# M5_Stick_YellowBox_Hat_2020-08-21_10-44-.net
KiCad netlist of a schematic drawn in EasyEDA
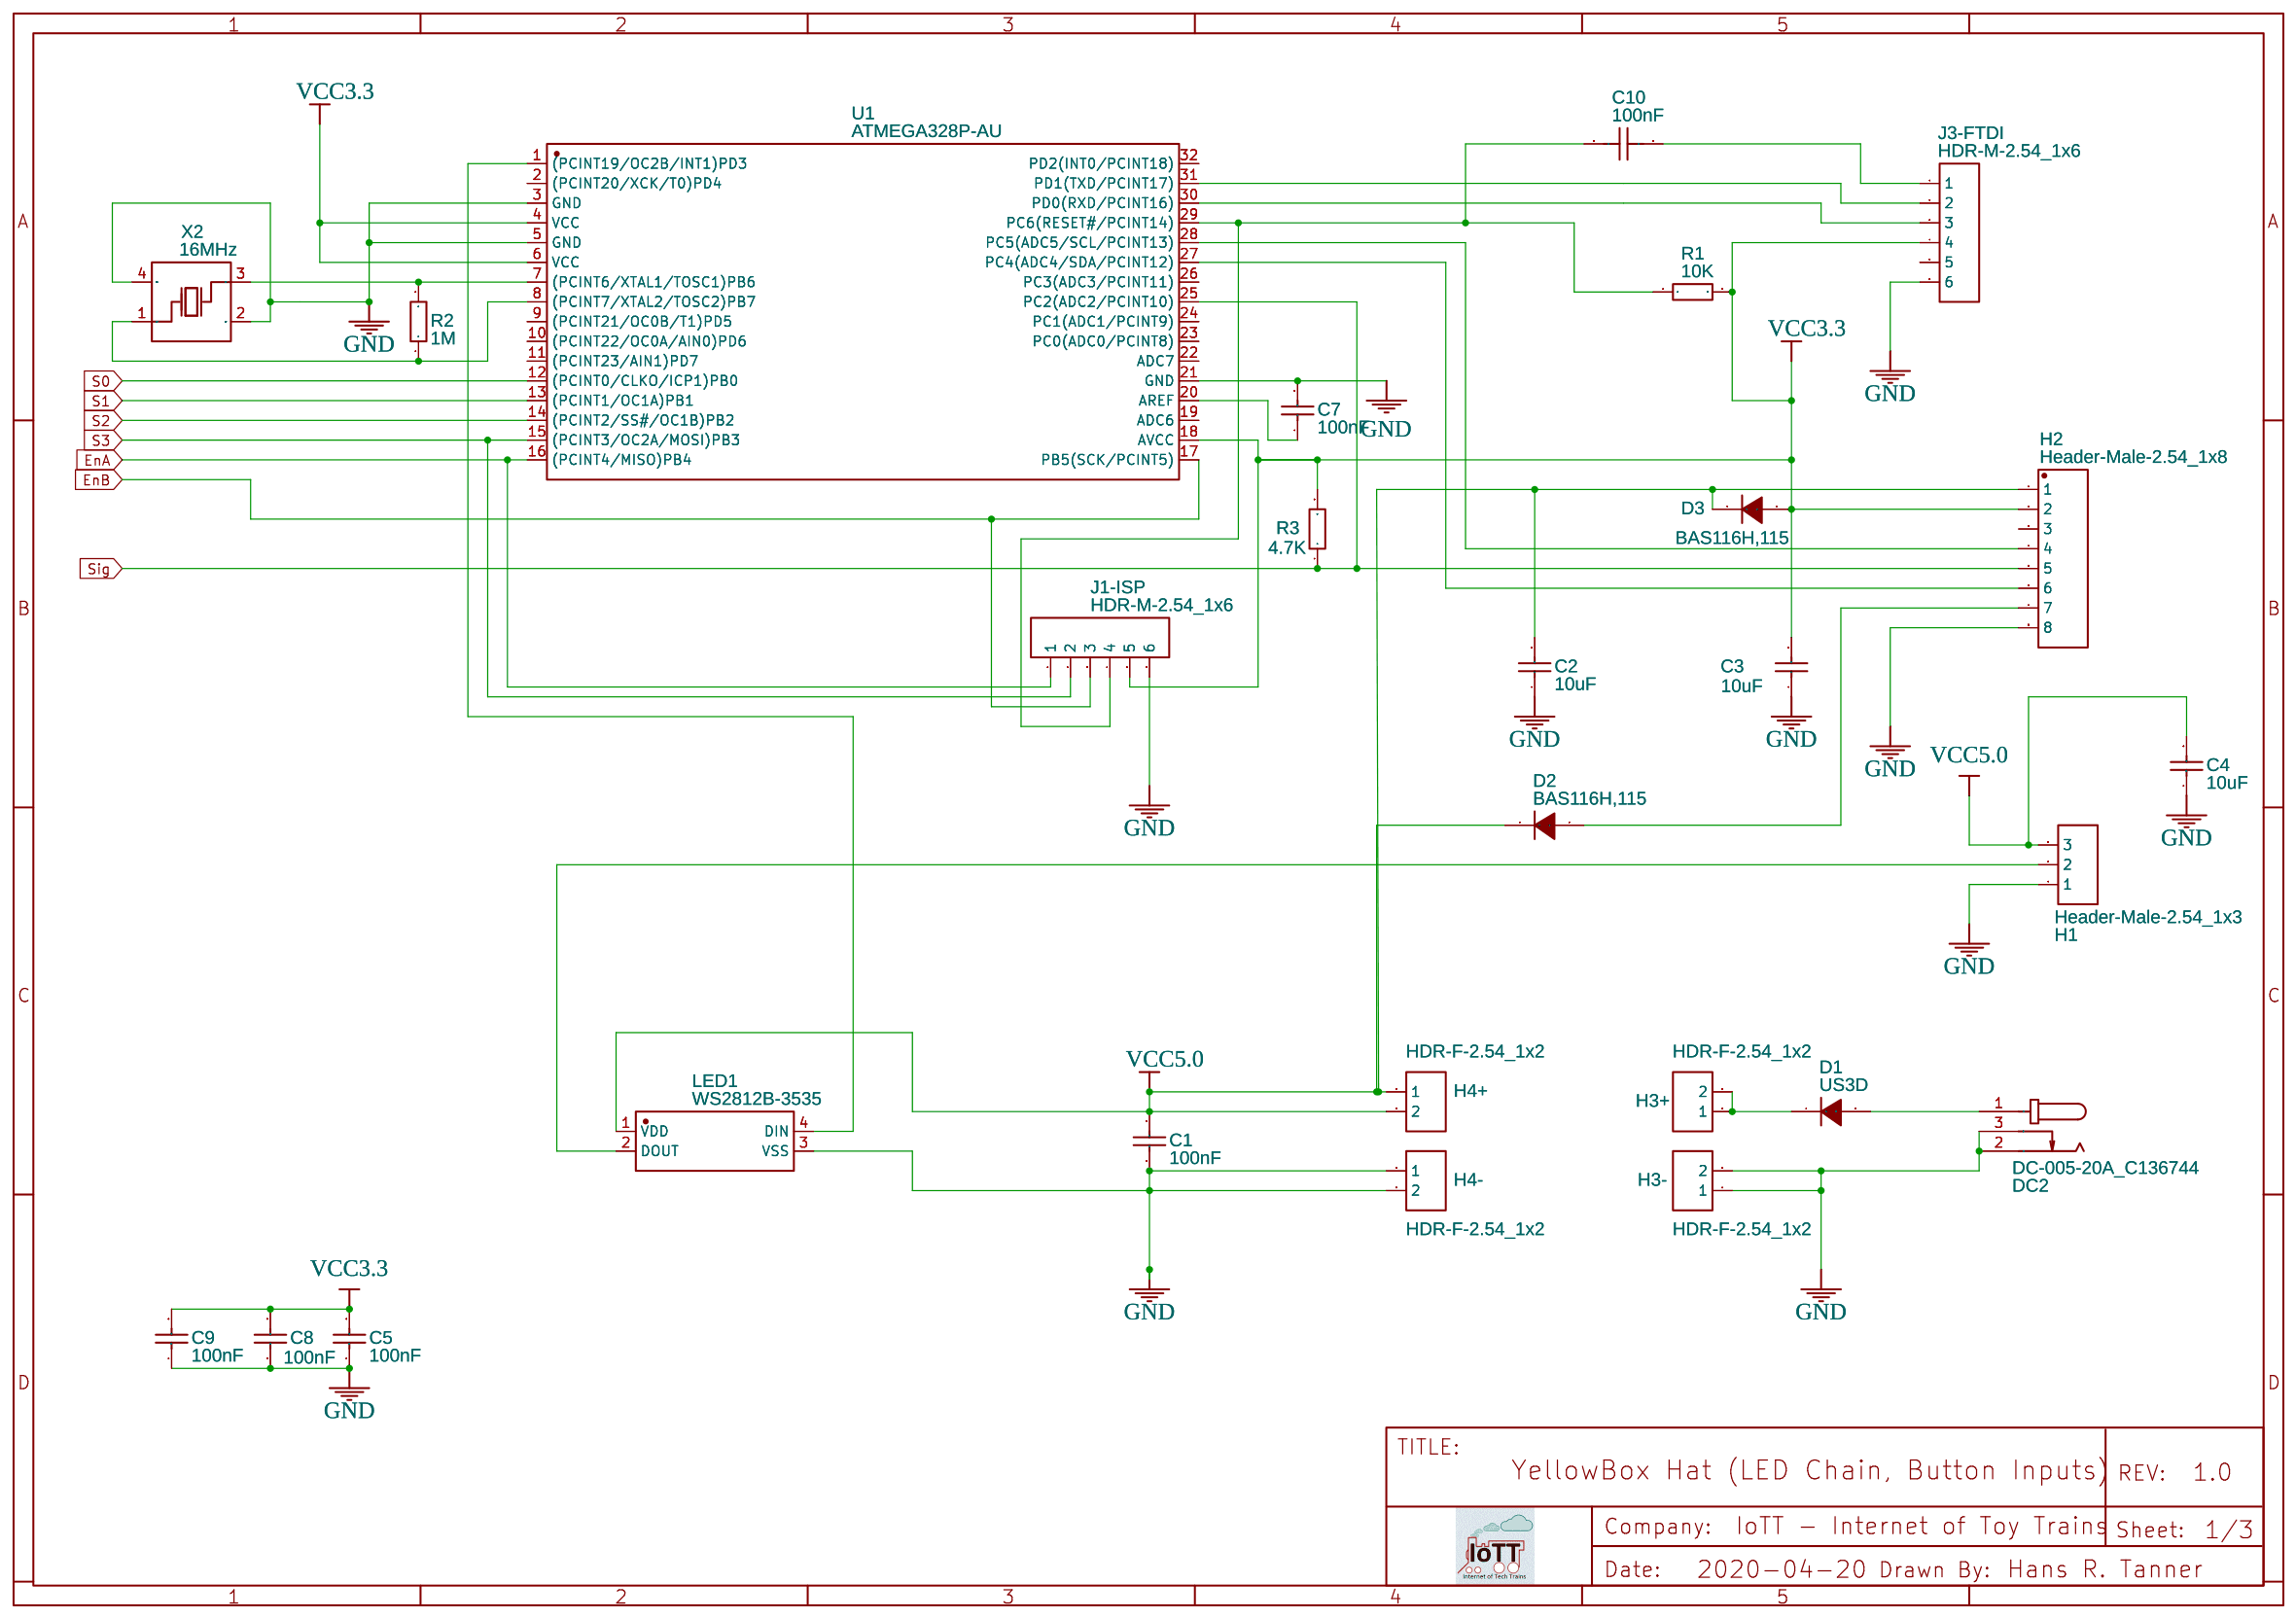
[diagram p0: YellowBox Hat P1]
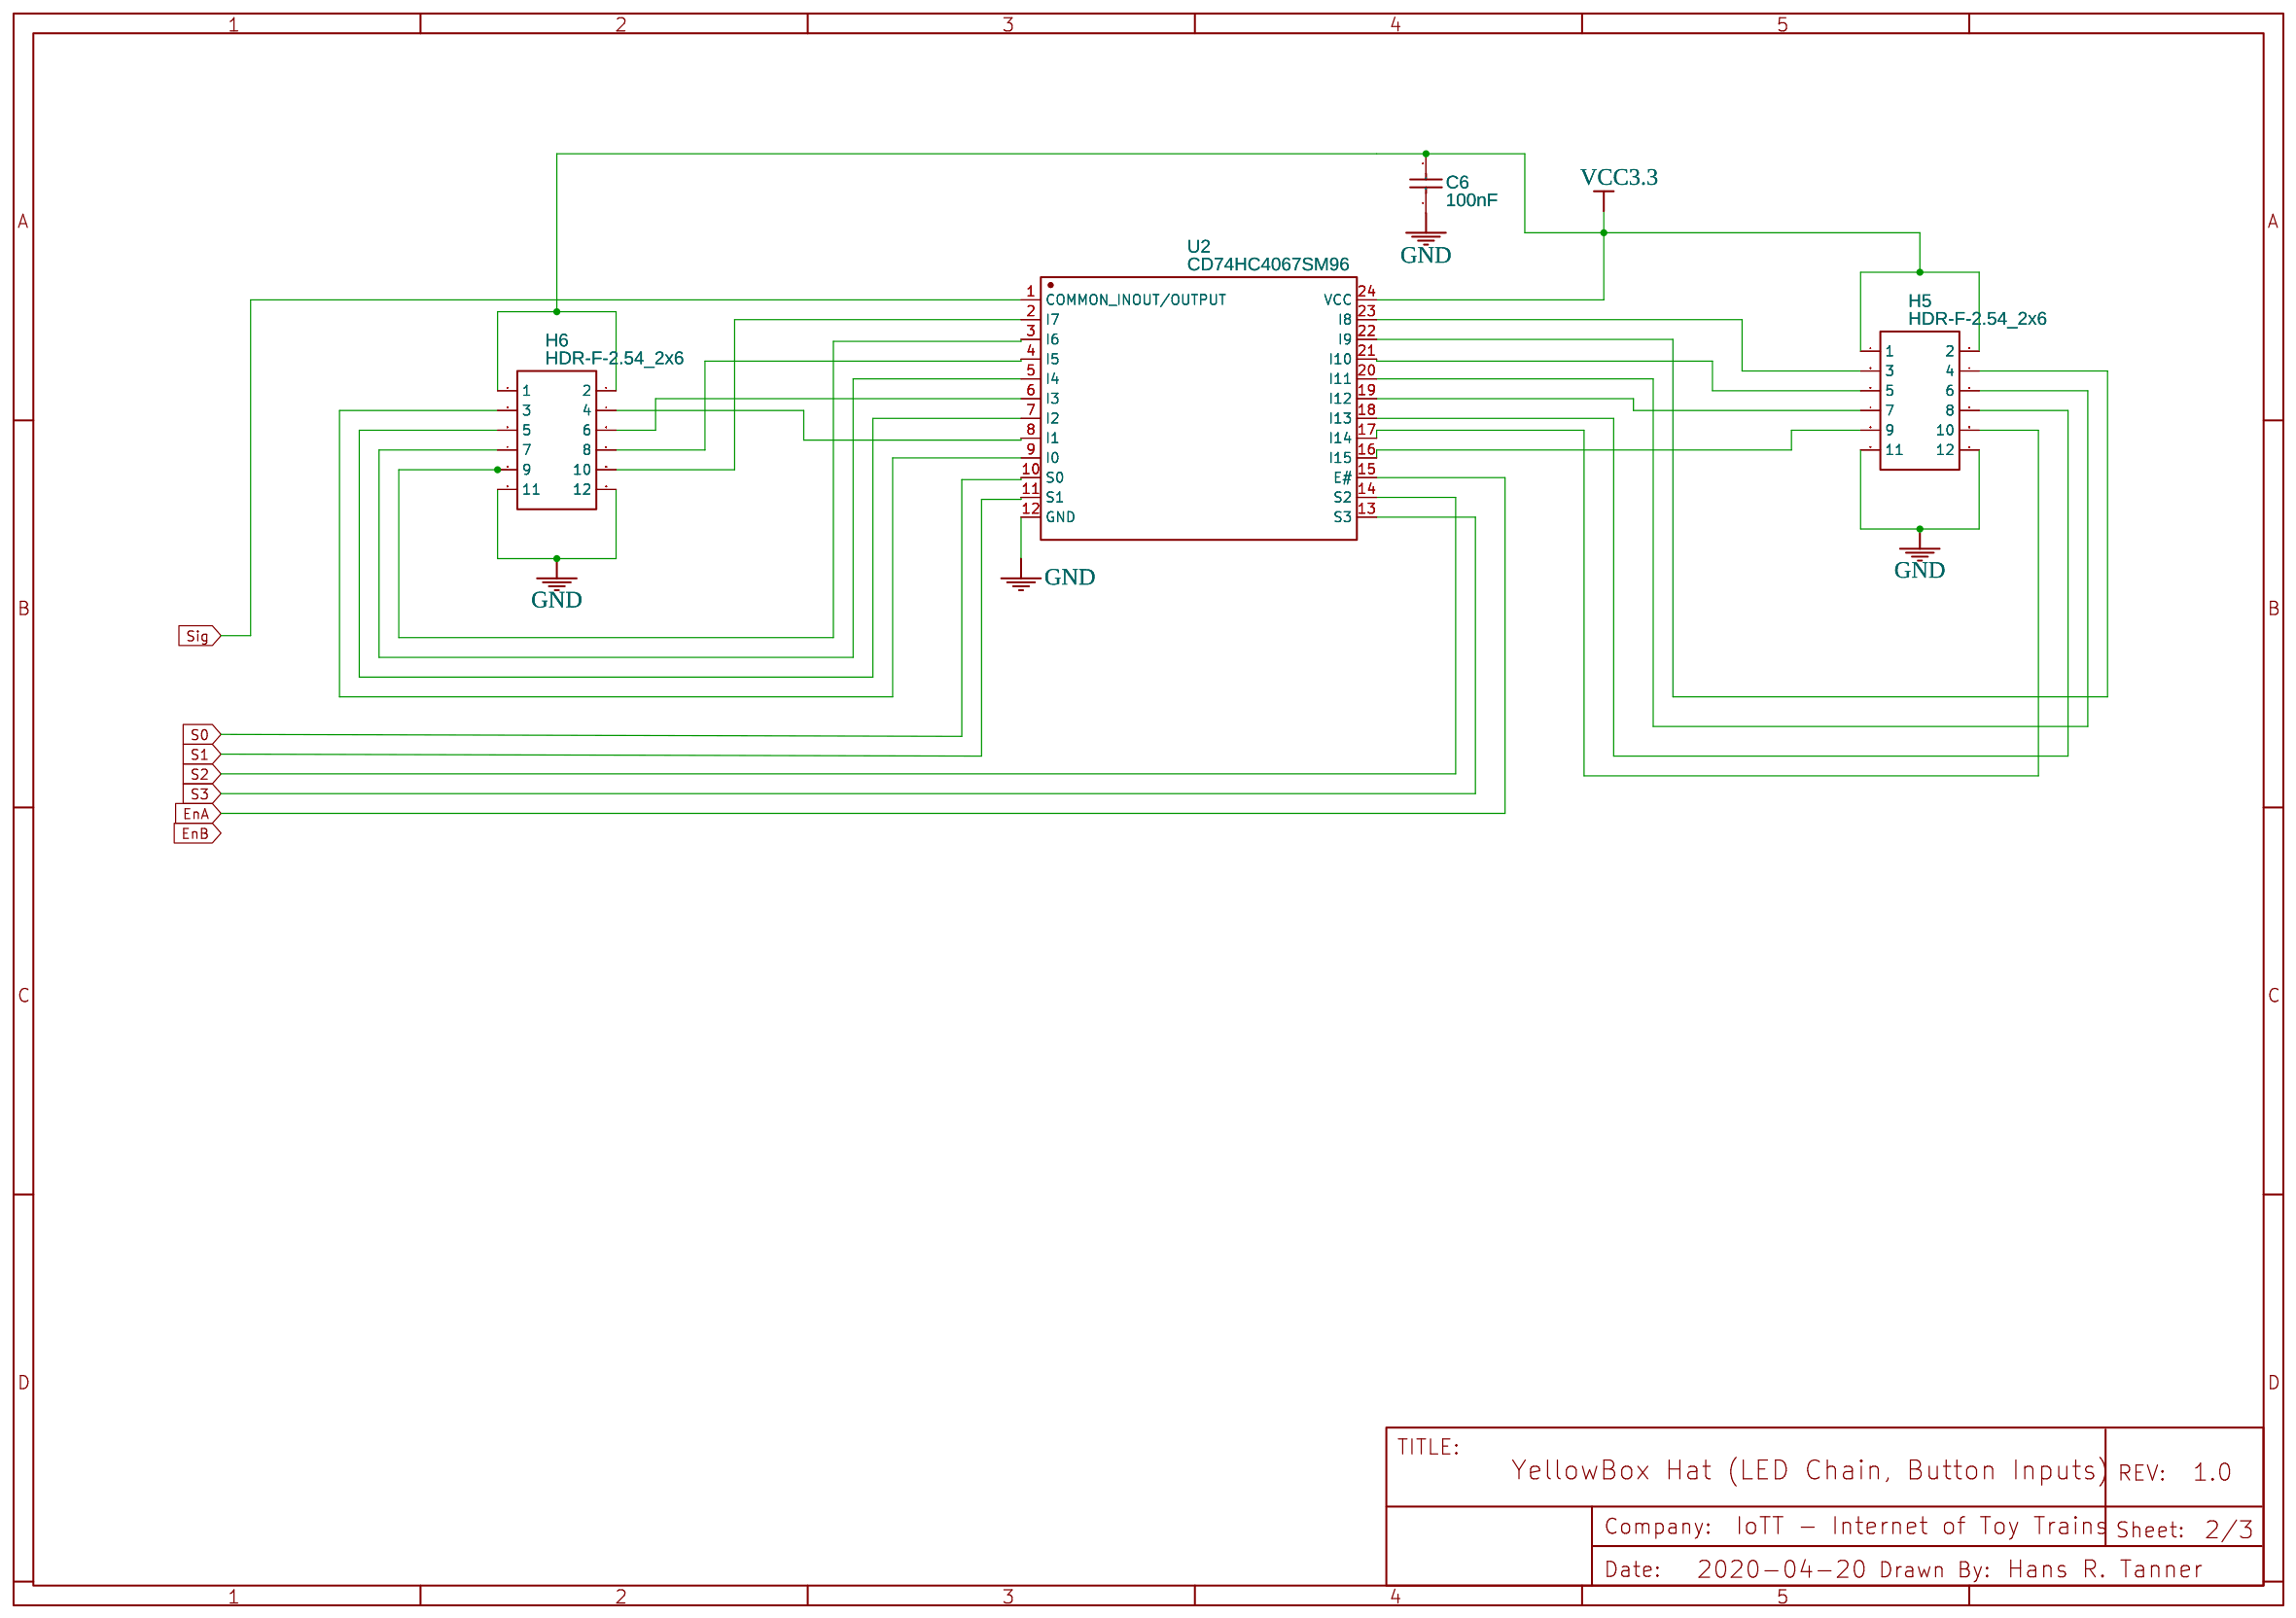
[diagram p1: YellowBox Hat P2]
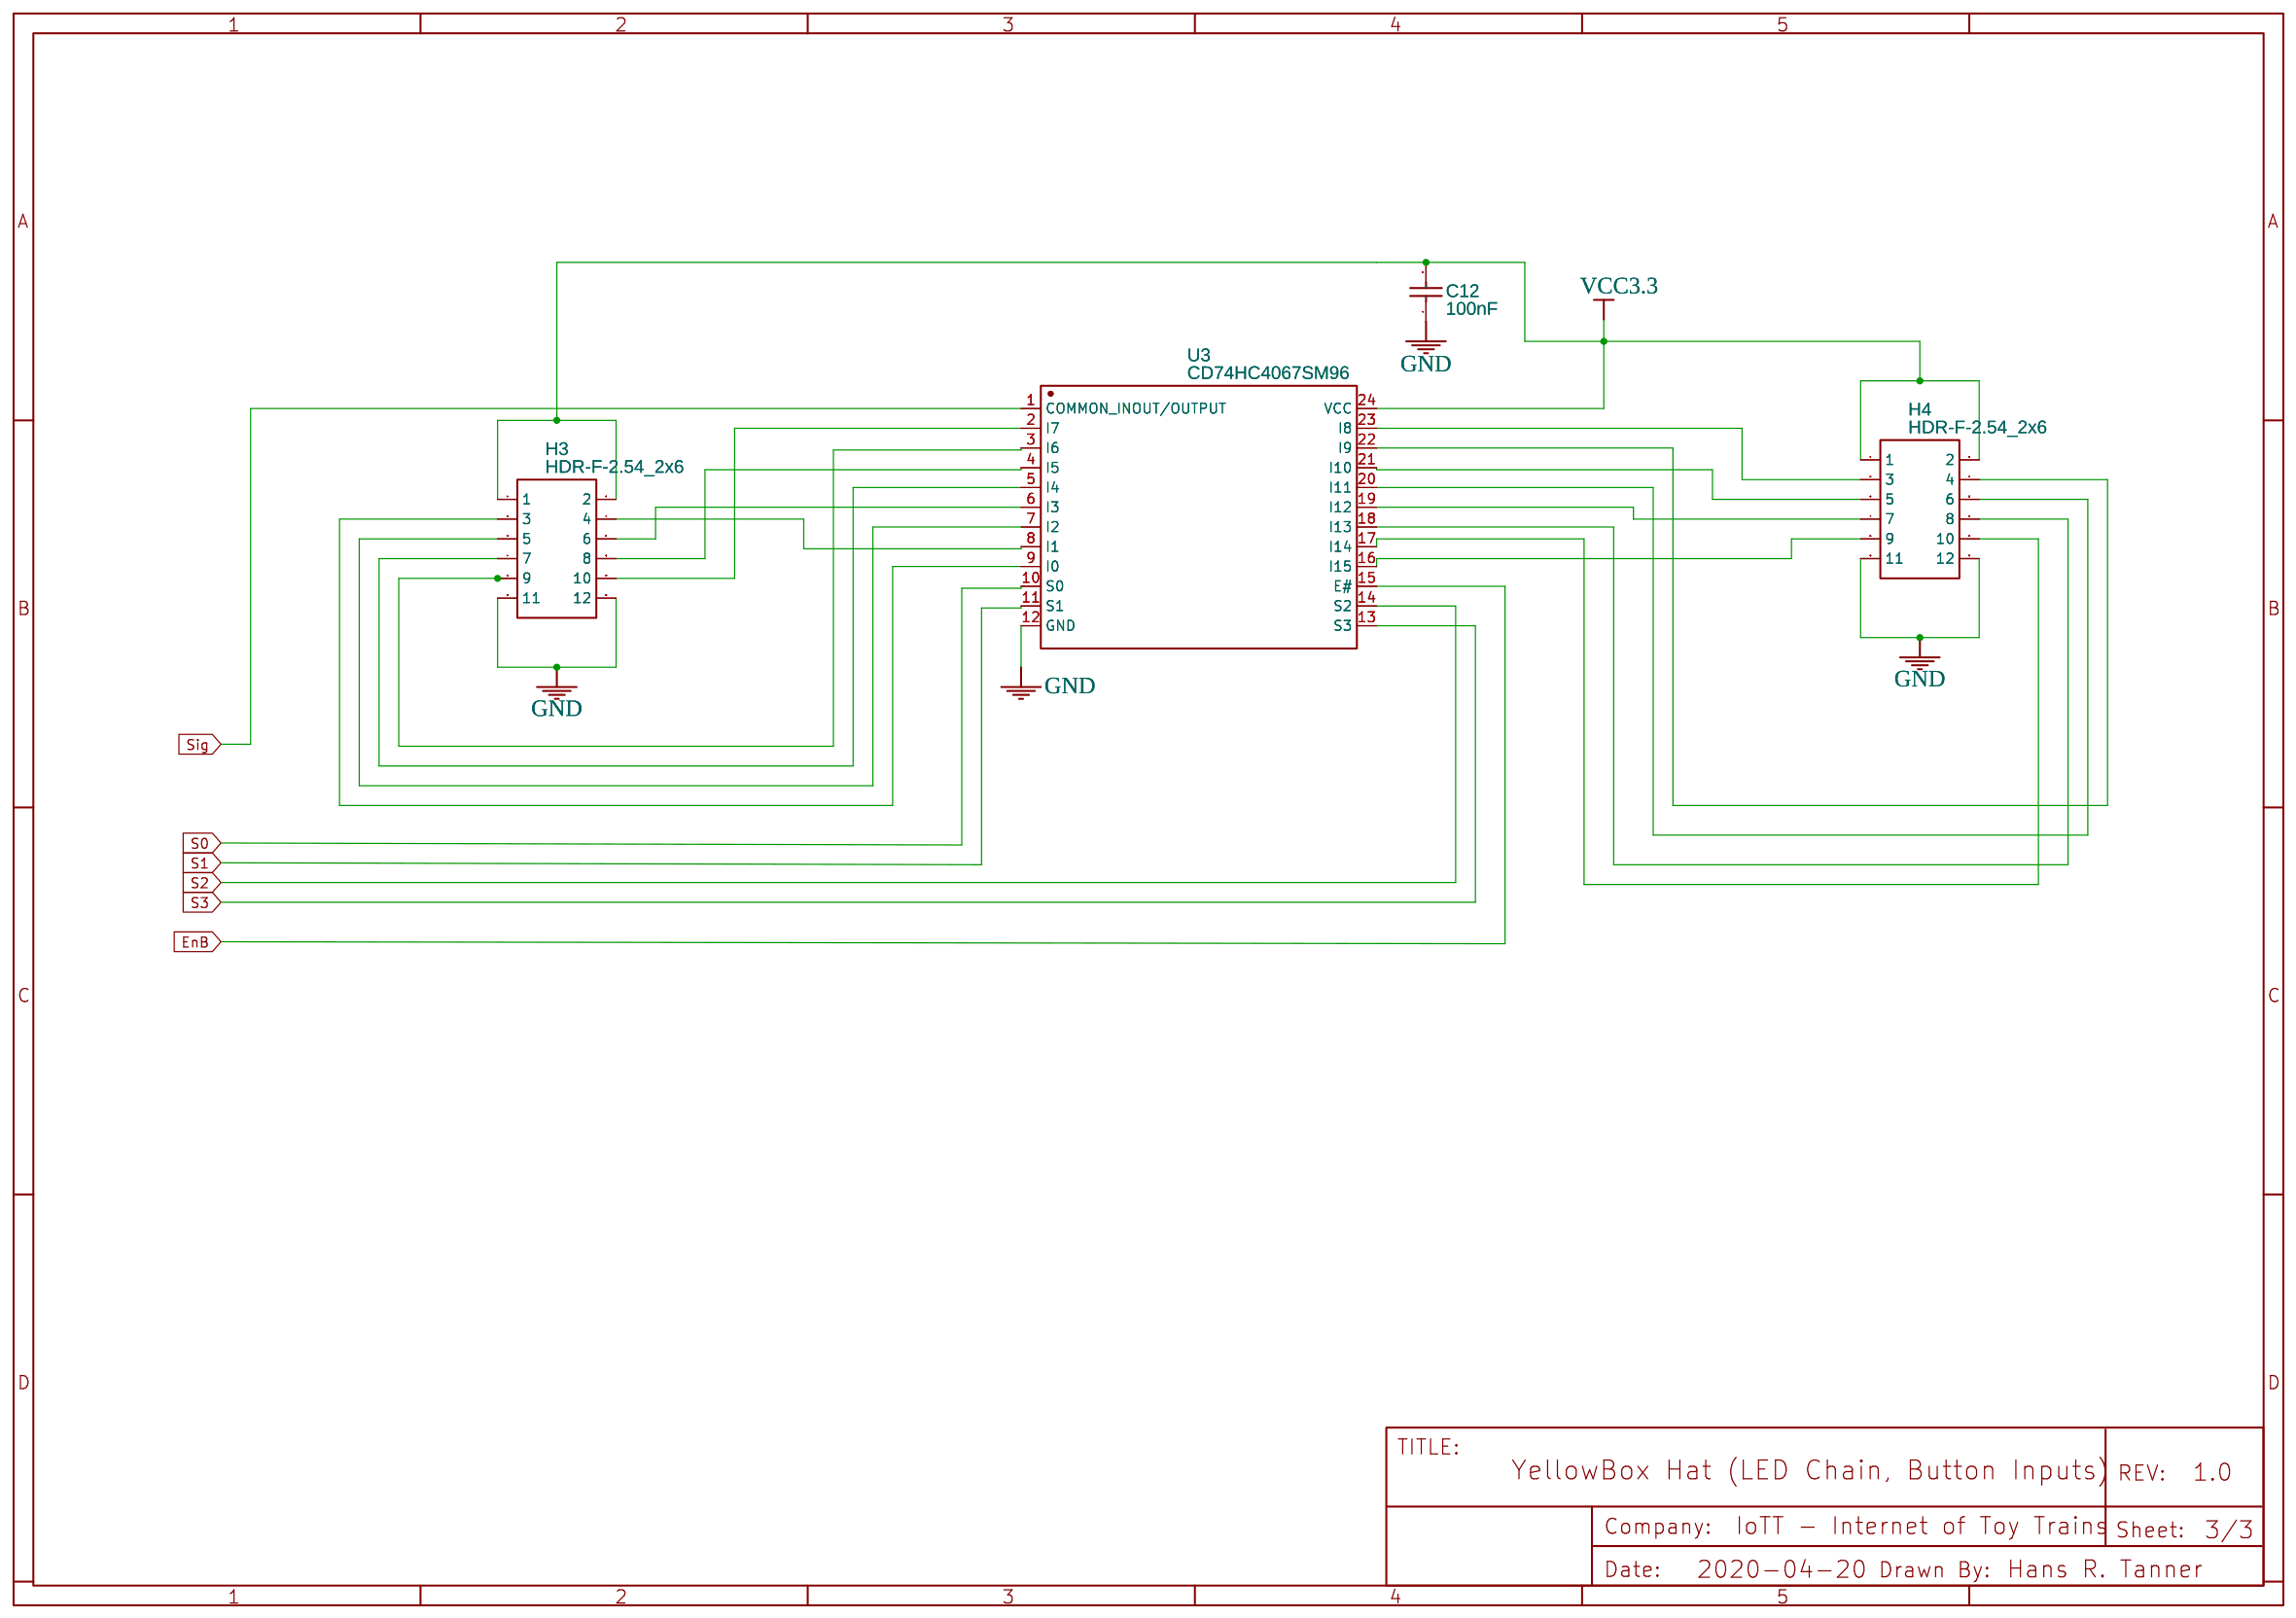
[diagram p2: YellowBox Hat P3]

(export (version "E")
  (design (tool "Eeschema 10.0.6"))
  (components
    (comp (ref "C1")
      (value "100nF")
      (fields
        (field (name "BOM_Manufacturer Part") "CL05B104KO5NNNC")
        (field (name "BOM_Supplier Part") "C1525")
      )
      (libsource (lib "") (part "CL05B104KO5NNNC"))
    )
    (comp (ref "C2")
      (value "10uF")
      (fields
        (field (name "BOM_Manufacturer Part") "CL21A106KAYNNNE")
        (field (name "BOM_Supplier Part") "C15850")
      )
      (libsource (lib "") (part "CL21A106KAYNNNE"))
    )
    (comp (ref "C3")
      (value "10uF")
      (fields
        (field (name "BOM_Manufacturer Part") "CL21A106KAYNNNE")
        (field (name "BOM_Supplier Part") "C15850")
      )
      (libsource (lib "") (part "CL21A106KAYNNNE"))
    )
    (comp (ref "C4")
      (value "10uF")
      (fields
        (field (name "BOM_Manufacturer Part") "CL21A106KAYNNNE")
        (field (name "BOM_Supplier Part") "C15850")
      )
      (libsource (lib "") (part "CL21A106KAYNNNE"))
    )
    (comp (ref "C5")
      (value "100nF")
      (fields
        (field (name "BOM_Manufacturer Part") "CL05B104KO5NNNC")
        (field (name "BOM_Supplier Part") "C1525")
      )
      (libsource (lib "") (part "CL05B104KO5NNNC"))
    )
    (comp (ref "C7")
      (value "100nF")
      (fields
        (field (name "BOM_Manufacturer Part") "CL05B104KO5NNNC")
        (field (name "BOM_Supplier Part") "C1525")
      )
      (libsource (lib "") (part "CL05B104KO5NNNC"))
    )
    (comp (ref "C8")
      (value "100nF")
      (fields
        (field (name "BOM_Manufacturer Part") "CL05B104KO5NNNC")
        (field (name "BOM_Supplier Part") "C1525")
      )
      (libsource (lib "") (part "CL05B104KO5NNNC"))
    )
    (comp (ref "C9")
      (value "100nF")
      (fields
        (field (name "BOM_Manufacturer Part") "CL05B104KO5NNNC")
        (field (name "BOM_Supplier Part") "C1525")
      )
      (libsource (lib "") (part "CL05B104KO5NNNC"))
    )
    (comp (ref "C10")
      (value "100nF")
      (fields
        (field (name "BOM_Manufacturer Part") "CC0603KRX7R9BB104")
        (field (name "BOM_Supplier Part") "C14663")
      )
      (libsource (lib "") (part "CC0603KRX7R9BB104"))
    )
    (comp (ref "D1")
      (value "US3D")
      (fields (field (name "BOM_Supplier Part") "C64964"))
      (libsource (lib "") (part "US3D"))
    )
    (comp (ref "D2")
      (value "BAS116H,115")
      (fields (field (name "BOM_Supplier Part") "C74210"))
      (libsource (lib "") (part "BAS116H,115"))
    )
    (comp (ref "D3")
      (value "BAS116H,115")
      (fields (field (name "BOM_Supplier Part") "C74210"))
      (libsource (lib "") (part "BAS116H,115"))
    )
    (comp (ref "DC2")
      (value "DC-005-20A_C136744")
      (fields
        (field (name "BOM_Manufacturer Part") "DC-005-20A")
        (field (name "BOM_Supplier Part") "C136744")
      )
      (libsource (lib "") (part "DC-005-20A_C136744"))
    )
    (comp (ref "H1")
      (value "Header-Male-2.54_1x3")
      (fields
        (field (name "BOM_Manufacturer Part") "Header2.54mm 1*3P")
        (field (name "BOM_Supplier Part") "C49257")
      )
      (libsource (lib "") (part "Header-Male-2.54_1x3"))
    )
    (comp (ref "H2")
      (value "Header-Male-2.54_1x8")
      (fields
        (field (name "BOM_Manufacturer Part") "210S-1*8P L=11.6MMGold-plated black")
        (field (name "BOM_Supplier Part") "C124381")
      )
      (libsource (lib "") (part "Header-Male-2.54_1x8"))
    )
    (comp (ref "H3+")
      (value "HDR-F-2.54_1x2")
      (fields (field (name "BOM_Supplier Part") "C49661"))
      (libsource (lib "") (part "HDR-F-2.54_1x2"))
    )
    (comp (ref "H3-")
      (value "HDR-F-2.54_1x2")
      (fields (field (name "BOM_Supplier Part") "C49661"))
      (libsource (lib "") (part "HDR-F-2.54_1x2_2"))
    )
    (comp (ref "H4+")
      (value "HDR-F-2.54_1x2")
      (fields (field (name "BOM_Supplier Part") "C49661"))
      (libsource (lib "") (part "HDR-F-2.54_1x2_3"))
    )
    (comp (ref "H4-")
      (value "HDR-F-2.54_1x2")
      (fields (field (name "BOM_Supplier Part") "C49661"))
      (libsource (lib "") (part "HDR-F-2.54_1x2_1"))
    )
    (comp (ref "J1-ISP")
      (value "HDR-M-2.54_1x6")
      (fields (field (name "BOM_Supplier Part") "C190819"))
      (libsource (lib "") (part "HDR-M-2.54_1x6"))
    )
    (comp (ref "J3-FTDI")
      (value "HDR-M-2.54_1x6")
      (fields (field (name "BOM_Supplier Part") "C190819"))
      (libsource (lib "") (part "HDR-M-2.54_1x6_1"))
    )
    (comp (ref "LED1")
      (value "WS2812B-3535")
      (fields (field (name "BOM_Supplier Part") "C114583"))
      (libsource (lib "") (part "WS2812B-3535"))
    )
    (comp (ref "R1")
      (value "10K")
      (fields
        (field (name "BOM_Manufacturer Part") "0402WGF1002TCE")
        (field (name "BOM_Supplier Part") "C25744")
      )
      (libsource (lib "") (part "0402WGF1002TCE"))
    )
    (comp (ref "R2")
      (value "1M")
      (fields
        (field (name "BOM_Manufacturer Part") "0402WGF1004TCE")
        (field (name "BOM_Supplier Part") "C26083")
      )
      (libsource (lib "") (part "0402WGF1004TCE"))
    )
    (comp (ref "R3")
      (value "4.7K")
      (fields
        (field (name "BOM_Manufacturer Part") "0603WAF4701T5E")
        (field (name "BOM_Supplier Part") "C23162")
      )
      (libsource (lib "") (part "0603WAF1001T5E"))
    )
    (comp (ref "U1")
      (value "ATMEGA328P-AU")
      (fields (field (name "BOM_Supplier Part") "C14877"))
      (libsource (lib "") (part "ATMEGA328P-AU"))
    )
    (comp (ref "X2")
      (value "16MHz")
      (fields
        (field (name "BOM_Manufacturer Part") "X322516MLB4SI")
        (field (name "BOM_Supplier Part") "C13738")
      )
      (libsource (lib "") (part "X322516MLB4SI"))
    )
    (comp (ref "C6")
      (value "100nF")
      (fields
        (field (name "BOM_Manufacturer Part") "CL05B104KO5NNNC")
        (field (name "BOM_Supplier Part") "C1525")
      )
      (libsource (lib "") (part "CL05B104KO5NNNC"))
    )
    (comp (ref "H5")
      (value "HDR-F-2.54_2x6")
      (fields (field (name "BOM_Supplier Part") "C36191"))
      (libsource (lib "") (part "HDR-F-2.54_2x6"))
    )
    (comp (ref "H6")
      (value "HDR-F-2.54_2x6")
      (fields (field (name "BOM_Supplier Part") "C36191"))
      (libsource (lib "") (part "HDR-F-2.54_2x6"))
    )
    (comp (ref "U2")
      (value "CD74HC4067SM96")
      (fields (field (name "BOM_Supplier Part") "C98457"))
      (libsource (lib "") (part "CD74HC4067SM96"))
    )
    (comp (ref "C12")
      (value "100nF")
      (fields
        (field (name "BOM_Manufacturer Part") "CL05B104KO5NNNC")
        (field (name "BOM_Supplier Part") "C1525")
      )
      (libsource (lib "") (part "CL05B104KO5NNNC"))
    )
    (comp (ref "H3")
      (value "HDR-F-2.54_2x6")
      (fields (field (name "BOM_Supplier Part") "C36191"))
      (libsource (lib "") (part "HDR-F-2.54_2x6"))
    )
    (comp (ref "H4")
      (value "HDR-F-2.54_2x6")
      (fields (field (name "BOM_Supplier Part") "C36191"))
      (libsource (lib "") (part "HDR-F-2.54_2x6"))
    )
    (comp (ref "U3")
      (value "CD74HC4067SM96")
      (fields (field (name "BOM_Supplier Part") "C98457"))
      (libsource (lib "") (part "CD74HC4067SM96"))
    )
  )
  (nets
    (net (code "1") (name "EnA") (class "Default")
      (node (ref "J1-ISP") (pin "1") (pinfunction "1_1") (pintype "input"))
      (node (ref "U1") (pin "16") (pinfunction "(PCINT4/MISO)PB4_16") (pintype "unspecified"))
      (node (ref "U2") (pin "15") (pinfunction "E#_15") (pintype "unspecified"))
    )
    (net (code "2") (name "EnB") (class "Default")
      (node (ref "J1-ISP") (pin "3") (pinfunction "3_3") (pintype "input"))
      (node (ref "U1") (pin "17") (pinfunction "PB5(SCK/PCINT5)_17") (pintype "unspecified"))
      (node (ref "U3") (pin "15") (pinfunction "E#_15") (pintype "unspecified"))
    )
    (net (code "3") (name "GND") (class "Default")
      (node (ref "C1") (pin "1") (pinfunction "1_1") (pintype "input"))
      (node (ref "C12") (pin "1") (pinfunction "1_1") (pintype "input"))
      (node (ref "C2") (pin "1") (pinfunction "1_1") (pintype "input"))
      (node (ref "C3") (pin "1") (pinfunction "1_1") (pintype "input"))
      (node (ref "C4") (pin "1") (pinfunction "1_1") (pintype "input"))
      (node (ref "C5") (pin "1") (pinfunction "1_1") (pintype "input"))
      (node (ref "C6") (pin "1") (pinfunction "1_1") (pintype "input"))
      (node (ref "C7") (pin "2") (pinfunction "2_2") (pintype "input"))
      (node (ref "C8") (pin "1") (pinfunction "1_1") (pintype "input"))
      (node (ref "C9") (pin "1") (pinfunction "1_1") (pintype "input"))
      (node (ref "DC2") (pin "2") (pinfunction "2_2") (pintype "unspecified"))
      (node (ref "DC2") (pin "3") (pinfunction "3_3") (pintype "unspecified"))
      (node (ref "H1") (pin "1") (pinfunction "1_1") (pintype "input"))
      (node (ref "H2") (pin "8") (pinfunction "8_8") (pintype "unspecified"))
      (node (ref "H3") (pin "11") (pinfunction "11_11") (pintype "input"))
      (node (ref "H3") (pin "12") (pinfunction "12_12") (pintype "input"))
      (node (ref "H3-") (pin "1") (pinfunction "1_1") (pintype "input"))
      (node (ref "H3-") (pin "2") (pinfunction "2_2") (pintype "input"))
      (node (ref "H4") (pin "11") (pinfunction "11_11") (pintype "input"))
      (node (ref "H4") (pin "12") (pinfunction "12_12") (pintype "input"))
      (node (ref "H4-") (pin "1") (pinfunction "1_1") (pintype "input"))
      (node (ref "H4-") (pin "2") (pinfunction "2_2") (pintype "input"))
      (node (ref "H5") (pin "11") (pinfunction "11_11") (pintype "input"))
      (node (ref "H5") (pin "12") (pinfunction "12_12") (pintype "input"))
      (node (ref "H6") (pin "11") (pinfunction "11_11") (pintype "input"))
      (node (ref "H6") (pin "12") (pinfunction "12_12") (pintype "input"))
      (node (ref "J1-ISP") (pin "6") (pinfunction "6_6") (pintype "input"))
      (node (ref "J3-FTDI") (pin "6") (pinfunction "6_6") (pintype "input"))
      (node (ref "LED1") (pin "3") (pinfunction "VSS_3") (pintype "unspecified"))
      (node (ref "U1") (pin "21") (pinfunction "GND_21") (pintype "unspecified"))
      (node (ref "U1") (pin "3") (pinfunction "GND_3") (pintype "unspecified"))
      (node (ref "U1") (pin "5") (pinfunction "GND_5") (pintype "unspecified"))
      (node (ref "U2") (pin "12") (pinfunction "GND_12") (pintype "unspecified"))
      (node (ref "U3") (pin "12") (pinfunction "GND_12") (pintype "unspecified"))
      (node (ref "X2") (pin "2") (pinfunction "GND_2") (pintype "unspecified"))
      (node (ref "X2") (pin "4") (pinfunction "GND_4") (pintype "unspecified"))
    )
    (net (code "4") (name "Net-(C10-Pad2)") (class "Default")
      (node (ref "C10") (pin "2") (pinfunction "2_2") (pintype "unspecified"))
      (node (ref "J3-FTDI") (pin "1") (pinfunction "1_1") (pintype "input"))
    )
    (net (code "5") (name "Net-(D1-Pad1)") (class "Default")
      (node (ref "D1") (pin "1") (pinfunction "1_1") (pintype "unspecified"))
      (node (ref "H3+") (pin "1") (pinfunction "1_1") (pintype "input"))
      (node (ref "H3+") (pin "2") (pinfunction "2_2") (pintype "input"))
    )
    (net (code "6") (name "Net-(D1-Pad2)") (class "Default")
      (node (ref "D1") (pin "2") (pinfunction "2_2") (pintype "unspecified"))
      (node (ref "DC2") (pin "1") (pinfunction "1_1") (pintype "unspecified"))
    )
    (net (code "7") (name "Net-(D2-A)") (class "Default")
      (node (ref "D2") (pin "2") (pinfunction "A_2") (pintype "unspecified"))
      (node (ref "H2") (pin "7") (pinfunction "7_7") (pintype "unspecified"))
    )
    (net (code "8") (name "Net-(LED1-DIN)") (class "Default")
      (node (ref "LED1") (pin "4") (pinfunction "DIN_4") (pintype "unspecified"))
      (node (ref "U1") (pin "1") (pinfunction "(PCINT19/OC2B/INT1)PD3_1") (pintype "unspecified"))
    )
    (net (code "9") (name "Net-(LED1-DOUT)") (class "Default")
      (node (ref "H1") (pin "2") (pinfunction "2_2") (pintype "input"))
      (node (ref "LED1") (pin "2") (pinfunction "DOUT_2") (pintype "unspecified"))
    )
    (net (code "10") (name "Net-(U1-(PCINT6{slash}XTAL1{slash}TOSC1)PB6)") (class "Default")
      (node (ref "R2") (pin "2") (pinfunction "2_2") (pintype "input"))
      (node (ref "U1") (pin "7") (pinfunction "(PCINT6/XTAL1/TOSC1)PB6_7") (pintype "unspecified"))
      (node (ref "X2") (pin "3") (pinfunction "OSC2_3") (pintype "unspecified"))
    )
    (net (code "11") (name "Net-(U1-(PCINT7{slash}XTAL2{slash}TOSC2)PB7)") (class "Default")
      (node (ref "R2") (pin "1") (pinfunction "1_1") (pintype "input"))
      (node (ref "U1") (pin "8") (pinfunction "(PCINT7/XTAL2/TOSC2)PB7_8") (pintype "unspecified"))
      (node (ref "X2") (pin "1") (pinfunction "OSC1_1") (pintype "unspecified"))
    )
    (net (code "12") (name "Net-(U1-AREF)") (class "Default")
      (node (ref "C7") (pin "1") (pinfunction "1_1") (pintype "input"))
      (node (ref "U1") (pin "20") (pinfunction "AREF_20") (pintype "unspecified"))
    )
    (net (code "13") (name "Net-(U1-PC4(ADC4{slash}SDA{slash}PCINT12))") (class "Default")
      (node (ref "H2") (pin "6") (pinfunction "6_6") (pintype "unspecified"))
      (node (ref "U1") (pin "27") (pinfunction "PC4(ADC4/SDA/PCINT12)_27") (pintype "unspecified"))
    )
    (net (code "14") (name "Net-(U1-PC5(ADC5{slash}SCL{slash}PCINT13))") (class "Default")
      (node (ref "H2") (pin "4") (pinfunction "4_4") (pintype "unspecified"))
      (node (ref "U1") (pin "28") (pinfunction "PC5(ADC5/SCL/PCINT13)_28") (pintype "unspecified"))
    )
    (net (code "15") (name "Net-(U1-PC6(RESET#{slash}PCINT14))") (class "Default")
      (node (ref "C10") (pin "1") (pinfunction "1_1") (pintype "unspecified"))
      (node (ref "J1-ISP") (pin "4") (pinfunction "4_4") (pintype "input"))
      (node (ref "R1") (pin "1") (pinfunction "1_1") (pintype "input"))
      (node (ref "U1") (pin "29") (pinfunction "PC6(RESET#/PCINT14)_29") (pintype "unspecified"))
    )
    (net (code "16") (name "Net-(U1-PD0(RXD{slash}PCINT16))") (class "Default")
      (node (ref "J3-FTDI") (pin "3") (pinfunction "3_3") (pintype "input"))
      (node (ref "U1") (pin "30") (pinfunction "PD0(RXD/PCINT16)_30") (pintype "unspecified"))
    )
    (net (code "17") (name "Net-(U1-PD1(TXD{slash}PCINT17))") (class "Default")
      (node (ref "J3-FTDI") (pin "2") (pinfunction "2_2") (pintype "input"))
      (node (ref "U1") (pin "31") (pinfunction "PD1(TXD/PCINT17)_31") (pintype "unspecified"))
    )
    (net (code "18") (name "Net-(U2-I0)") (class "Default")
      (node (ref "H6") (pin "3") (pinfunction "3_3") (pintype "input"))
      (node (ref "U2") (pin "9") (pinfunction "I0_9") (pintype "unspecified"))
    )
    (net (code "19") (name "Net-(U2-I1)") (class "Default")
      (node (ref "H6") (pin "4") (pinfunction "4_4") (pintype "input"))
      (node (ref "U2") (pin "8") (pinfunction "I1_8") (pintype "unspecified"))
    )
    (net (code "20") (name "Net-(U2-I2)") (class "Default")
      (node (ref "H6") (pin "5") (pinfunction "5_5") (pintype "input"))
      (node (ref "U2") (pin "7") (pinfunction "I2_7") (pintype "unspecified"))
    )
    (net (code "21") (name "Net-(U2-I3)") (class "Default")
      (node (ref "H6") (pin "6") (pinfunction "6_6") (pintype "input"))
      (node (ref "U2") (pin "6") (pinfunction "I3_6") (pintype "unspecified"))
    )
    (net (code "22") (name "Net-(U2-I4)") (class "Default")
      (node (ref "H6") (pin "7") (pinfunction "7_7") (pintype "input"))
      (node (ref "U2") (pin "5") (pinfunction "I4_5") (pintype "unspecified"))
    )
    (net (code "23") (name "Net-(U2-I5)") (class "Default")
      (node (ref "H6") (pin "8") (pinfunction "8_8") (pintype "input"))
      (node (ref "U2") (pin "4") (pinfunction "I5_4") (pintype "unspecified"))
    )
    (net (code "24") (name "Net-(U2-I6)") (class "Default")
      (node (ref "H6") (pin "9") (pinfunction "9_9") (pintype "input"))
      (node (ref "U2") (pin "3") (pinfunction "I6_3") (pintype "unspecified"))
    )
    (net (code "25") (name "Net-(U2-I7)") (class "Default")
      (node (ref "H6") (pin "10") (pinfunction "10_10") (pintype "input"))
      (node (ref "U2") (pin "2") (pinfunction "I7_2") (pintype "unspecified"))
    )
    (net (code "26") (name "Net-(U2-I8)") (class "Default")
      (node (ref "H5") (pin "3") (pinfunction "3_3") (pintype "input"))
      (node (ref "U2") (pin "23") (pinfunction "I8_23") (pintype "unspecified"))
    )
    (net (code "27") (name "Net-(U2-I9)") (class "Default")
      (node (ref "H5") (pin "4") (pinfunction "4_4") (pintype "input"))
      (node (ref "U2") (pin "22") (pinfunction "I9_22") (pintype "unspecified"))
    )
    (net (code "28") (name "Net-(U2-I10)") (class "Default")
      (node (ref "H5") (pin "5") (pinfunction "5_5") (pintype "input"))
      (node (ref "U2") (pin "21") (pinfunction "I10_21") (pintype "unspecified"))
    )
    (net (code "29") (name "Net-(U2-I11)") (class "Default")
      (node (ref "H5") (pin "6") (pinfunction "6_6") (pintype "input"))
      (node (ref "U2") (pin "20") (pinfunction "I11_20") (pintype "unspecified"))
    )
    (net (code "30") (name "Net-(U2-I12)") (class "Default")
      (node (ref "H5") (pin "7") (pinfunction "7_7") (pintype "input"))
      (node (ref "U2") (pin "19") (pinfunction "I12_19") (pintype "unspecified"))
    )
    (net (code "31") (name "Net-(U2-I13)") (class "Default")
      (node (ref "H5") (pin "8") (pinfunction "8_8") (pintype "input"))
      (node (ref "U2") (pin "18") (pinfunction "I13_18") (pintype "unspecified"))
    )
    (net (code "32") (name "Net-(U2-I14)") (class "Default")
      (node (ref "H5") (pin "10") (pinfunction "10_10") (pintype "input"))
      (node (ref "U2") (pin "17") (pinfunction "I14_17") (pintype "unspecified"))
    )
    (net (code "33") (name "Net-(U2-I15)") (class "Default")
      (node (ref "H5") (pin "9") (pinfunction "9_9") (pintype "input"))
      (node (ref "U2") (pin "16") (pinfunction "I15_16") (pintype "unspecified"))
    )
    (net (code "34") (name "Net-(U3-I0)") (class "Default")
      (node (ref "H3") (pin "3") (pinfunction "3_3") (pintype "input"))
      (node (ref "U3") (pin "9") (pinfunction "I0_9") (pintype "unspecified"))
    )
    (net (code "35") (name "Net-(U3-I1)") (class "Default")
      (node (ref "H3") (pin "4") (pinfunction "4_4") (pintype "input"))
      (node (ref "U3") (pin "8") (pinfunction "I1_8") (pintype "unspecified"))
    )
    (net (code "36") (name "Net-(U3-I2)") (class "Default")
      (node (ref "H3") (pin "5") (pinfunction "5_5") (pintype "input"))
      (node (ref "U3") (pin "7") (pinfunction "I2_7") (pintype "unspecified"))
    )
    (net (code "37") (name "Net-(U3-I3)") (class "Default")
      (node (ref "H3") (pin "6") (pinfunction "6_6") (pintype "input"))
      (node (ref "U3") (pin "6") (pinfunction "I3_6") (pintype "unspecified"))
    )
    (net (code "38") (name "Net-(U3-I4)") (class "Default")
      (node (ref "H3") (pin "7") (pinfunction "7_7") (pintype "input"))
      (node (ref "U3") (pin "5") (pinfunction "I4_5") (pintype "unspecified"))
    )
    (net (code "39") (name "Net-(U3-I5)") (class "Default")
      (node (ref "H3") (pin "8") (pinfunction "8_8") (pintype "input"))
      (node (ref "U3") (pin "4") (pinfunction "I5_4") (pintype "unspecified"))
    )
    (net (code "40") (name "Net-(U3-I6)") (class "Default")
      (node (ref "H3") (pin "9") (pinfunction "9_9") (pintype "input"))
      (node (ref "U3") (pin "3") (pinfunction "I6_3") (pintype "unspecified"))
    )
    (net (code "41") (name "Net-(U3-I7)") (class "Default")
      (node (ref "H3") (pin "10") (pinfunction "10_10") (pintype "input"))
      (node (ref "U3") (pin "2") (pinfunction "I7_2") (pintype "unspecified"))
    )
    (net (code "42") (name "Net-(U3-I8)") (class "Default")
      (node (ref "H4") (pin "3") (pinfunction "3_3") (pintype "input"))
      (node (ref "U3") (pin "23") (pinfunction "I8_23") (pintype "unspecified"))
    )
    (net (code "43") (name "Net-(U3-I9)") (class "Default")
      (node (ref "H4") (pin "4") (pinfunction "4_4") (pintype "input"))
      (node (ref "U3") (pin "22") (pinfunction "I9_22") (pintype "unspecified"))
    )
    (net (code "44") (name "Net-(U3-I10)") (class "Default")
      (node (ref "H4") (pin "5") (pinfunction "5_5") (pintype "input"))
      (node (ref "U3") (pin "21") (pinfunction "I10_21") (pintype "unspecified"))
    )
    (net (code "45") (name "Net-(U3-I11)") (class "Default")
      (node (ref "H4") (pin "6") (pinfunction "6_6") (pintype "input"))
      (node (ref "U3") (pin "20") (pinfunction "I11_20") (pintype "unspecified"))
    )
    (net (code "46") (name "Net-(U3-I12)") (class "Default")
      (node (ref "H4") (pin "7") (pinfunction "7_7") (pintype "input"))
      (node (ref "U3") (pin "19") (pinfunction "I12_19") (pintype "unspecified"))
    )
    (net (code "47") (name "Net-(U3-I13)") (class "Default")
      (node (ref "H4") (pin "8") (pinfunction "8_8") (pintype "input"))
      (node (ref "U3") (pin "18") (pinfunction "I13_18") (pintype "unspecified"))
    )
    (net (code "48") (name "Net-(U3-I14)") (class "Default")
      (node (ref "H4") (pin "10") (pinfunction "10_10") (pintype "input"))
      (node (ref "U3") (pin "17") (pinfunction "I14_17") (pintype "unspecified"))
    )
    (net (code "49") (name "Net-(U3-I15)") (class "Default")
      (node (ref "H4") (pin "9") (pinfunction "9_9") (pintype "input"))
      (node (ref "U3") (pin "16") (pinfunction "I15_16") (pintype "unspecified"))
    )
    (net (code "50") (name "S0") (class "Default")
      (node (ref "U1") (pin "12") (pinfunction "(PCINT0/CLKO/ICP1)PB0_12") (pintype "unspecified"))
      (node (ref "U2") (pin "10") (pinfunction "S0_10") (pintype "unspecified"))
      (node (ref "U3") (pin "10") (pinfunction "S0_10") (pintype "unspecified"))
    )
    (net (code "51") (name "S1") (class "Default")
      (node (ref "U1") (pin "13") (pinfunction "(PCINT1/OC1A)PB1_13") (pintype "unspecified"))
      (node (ref "U2") (pin "11") (pinfunction "S1_11") (pintype "unspecified"))
      (node (ref "U3") (pin "11") (pinfunction "S1_11") (pintype "unspecified"))
    )
    (net (code "52") (name "S2") (class "Default")
      (node (ref "U1") (pin "14") (pinfunction "(PCINT2/SS#/OC1B)PB2_14") (pintype "unspecified"))
      (node (ref "U2") (pin "14") (pinfunction "S2_14") (pintype "unspecified"))
      (node (ref "U3") (pin "14") (pinfunction "S2_14") (pintype "unspecified"))
    )
    (net (code "53") (name "S3") (class "Default")
      (node (ref "J1-ISP") (pin "2") (pinfunction "2_2") (pintype "input"))
      (node (ref "U1") (pin "15") (pinfunction "(PCINT3/OC2A/MOSI)PB3_15") (pintype "unspecified"))
      (node (ref "U2") (pin "13") (pinfunction "S3_13") (pintype "unspecified"))
      (node (ref "U3") (pin "13") (pinfunction "S3_13") (pintype "unspecified"))
    )
    (net (code "54") (name "Sig") (class "Default")
      (node (ref "H2") (pin "5") (pinfunction "5_5") (pintype "unspecified"))
      (node (ref "R3") (pin "1") (pinfunction "1_1") (pintype "input"))
      (node (ref "U1") (pin "25") (pinfunction "PC2(ADC2/PCINT10)_25") (pintype "unspecified"))
      (node (ref "U2") (pin "1") (pinfunction "COMMON_INOUT/OUTPUT_1") (pintype "unspecified"))
      (node (ref "U3") (pin "1") (pinfunction "COMMON_INOUT/OUTPUT_1") (pintype "unspecified"))
    )
    (net (code "55") (name "VCC3.3") (class "Default")
      (node (ref "C12") (pin "2") (pinfunction "2_2") (pintype "input"))
      (node (ref "C3") (pin "2") (pinfunction "2_2") (pintype "input"))
      (node (ref "C5") (pin "2") (pinfunction "2_2") (pintype "input"))
      (node (ref "C6") (pin "2") (pinfunction "2_2") (pintype "input"))
      (node (ref "C8") (pin "2") (pinfunction "2_2") (pintype "input"))
      (node (ref "C9") (pin "2") (pinfunction "2_2") (pintype "input"))
      (node (ref "D3") (pin "2") (pinfunction "A_2") (pintype "unspecified"))
      (node (ref "H2") (pin "2") (pinfunction "2_2") (pintype "unspecified"))
      (node (ref "H3") (pin "1") (pinfunction "1_1") (pintype "input"))
      (node (ref "H3") (pin "2") (pinfunction "2_2") (pintype "input"))
      (node (ref "H4") (pin "1") (pinfunction "1_1") (pintype "input"))
      (node (ref "H4") (pin "2") (pinfunction "2_2") (pintype "input"))
      (node (ref "H5") (pin "1") (pinfunction "1_1") (pintype "input"))
      (node (ref "H5") (pin "2") (pinfunction "2_2") (pintype "input"))
      (node (ref "H6") (pin "1") (pinfunction "1_1") (pintype "input"))
      (node (ref "H6") (pin "2") (pinfunction "2_2") (pintype "input"))
      (node (ref "J1-ISP") (pin "5") (pinfunction "5_5") (pintype "input"))
      (node (ref "J3-FTDI") (pin "4") (pinfunction "4_4") (pintype "input"))
      (node (ref "R1") (pin "2") (pinfunction "2_2") (pintype "input"))
      (node (ref "R3") (pin "2") (pinfunction "2_2") (pintype "input"))
      (node (ref "U1") (pin "18") (pinfunction "AVCC_18") (pintype "unspecified"))
      (node (ref "U1") (pin "4") (pinfunction "VCC_4") (pintype "unspecified"))
      (node (ref "U1") (pin "6") (pinfunction "VCC_6") (pintype "unspecified"))
      (node (ref "U2") (pin "24") (pinfunction "VCC_24") (pintype "unspecified"))
      (node (ref "U3") (pin "24") (pinfunction "VCC_24") (pintype "unspecified"))
    )
    (net (code "56") (name "VCC5.0") (class "Default")
      (node (ref "C1") (pin "2") (pinfunction "2_2") (pintype "input"))
      (node (ref "C2") (pin "2") (pinfunction "2_2") (pintype "input"))
      (node (ref "C4") (pin "2") (pinfunction "2_2") (pintype "input"))
      (node (ref "D2") (pin "1") (pinfunction "K_1") (pintype "unspecified"))
      (node (ref "D3") (pin "1") (pinfunction "K_1") (pintype "unspecified"))
      (node (ref "H1") (pin "3") (pinfunction "3_3") (pintype "input"))
      (node (ref "H2") (pin "1") (pinfunction "1_1") (pintype "unspecified"))
      (node (ref "H4+") (pin "1") (pinfunction "1_1") (pintype "input"))
      (node (ref "H4+") (pin "2") (pinfunction "2_2") (pintype "input"))
      (node (ref "LED1") (pin "1") (pinfunction "VDD_1") (pintype "unspecified"))
    )
    (net (code "57") (name "unconnected-(H2-Pad3)") (class "Default")
      (node (ref "H2") (pin "3") (pinfunction "3_3") (pintype "unspecified"))
    )
    (net (code "58") (name "unconnected-(J3-FTDI-Pad5)") (class "Default")
      (node (ref "J3-FTDI") (pin "5") (pinfunction "5_5") (pintype "input"))
    )
    (net (code "59") (name "unconnected-(U1-(PCINT20{slash}XCK{slash}T0)PD4-Pad2)") (class "Default")
      (node (ref "U1") (pin "2") (pinfunction "(PCINT20/XCK/T0)PD4_2") (pintype "unspecified"))
    )
    (net (code "60") (name "unconnected-(U1-(PCINT21{slash}OC0B{slash}T1)PD5-Pad9)") (class "Default")
      (node (ref "U1") (pin "9") (pinfunction "(PCINT21/OC0B/T1)PD5_9") (pintype "unspecified"))
    )
    (net (code "61") (name "unconnected-(U1-(PCINT22{slash}OC0A{slash}AIN0)PD6-Pad10)") (class "Default")
      (node (ref "U1") (pin "10") (pinfunction "(PCINT22/OC0A/AIN0)PD6_10") (pintype "unspecified"))
    )
    (net (code "62") (name "unconnected-(U1-(PCINT23{slash}AIN1)PD7-Pad11)") (class "Default")
      (node (ref "U1") (pin "11") (pinfunction "(PCINT23/AIN1)PD7_11") (pintype "unspecified"))
    )
    (net (code "63") (name "unconnected-(U1-ADC6-Pad19)") (class "Default")
      (node (ref "U1") (pin "19") (pinfunction "ADC6_19") (pintype "unspecified"))
    )
    (net (code "64") (name "unconnected-(U1-ADC7-Pad22)") (class "Default")
      (node (ref "U1") (pin "22") (pinfunction "ADC7_22") (pintype "unspecified"))
    )
    (net (code "65") (name "unconnected-(U1-PC0(ADC0{slash}PCINT8)-Pad23)") (class "Default")
      (node (ref "U1") (pin "23") (pinfunction "PC0(ADC0/PCINT8)_23") (pintype "unspecified"))
    )
    (net (code "66") (name "unconnected-(U1-PC1(ADC1{slash}PCINT9)-Pad24)") (class "Default")
      (node (ref "U1") (pin "24") (pinfunction "PC1(ADC1/PCINT9)_24") (pintype "unspecified"))
    )
    (net (code "67") (name "unconnected-(U1-PC3(ADC3{slash}PCINT11)-Pad26)") (class "Default")
      (node (ref "U1") (pin "26") (pinfunction "PC3(ADC3/PCINT11)_26") (pintype "unspecified"))
    )
    (net (code "68") (name "unconnected-(U1-PD2(INT0{slash}PCINT18)-Pad32)") (class "Default")
      (node (ref "U1") (pin "32") (pinfunction "PD2(INT0/PCINT18)_32") (pintype "unspecified"))
    )
  )
)
